# SER_24.net
KiCad netlist of a schematic drawn in Altium Designer
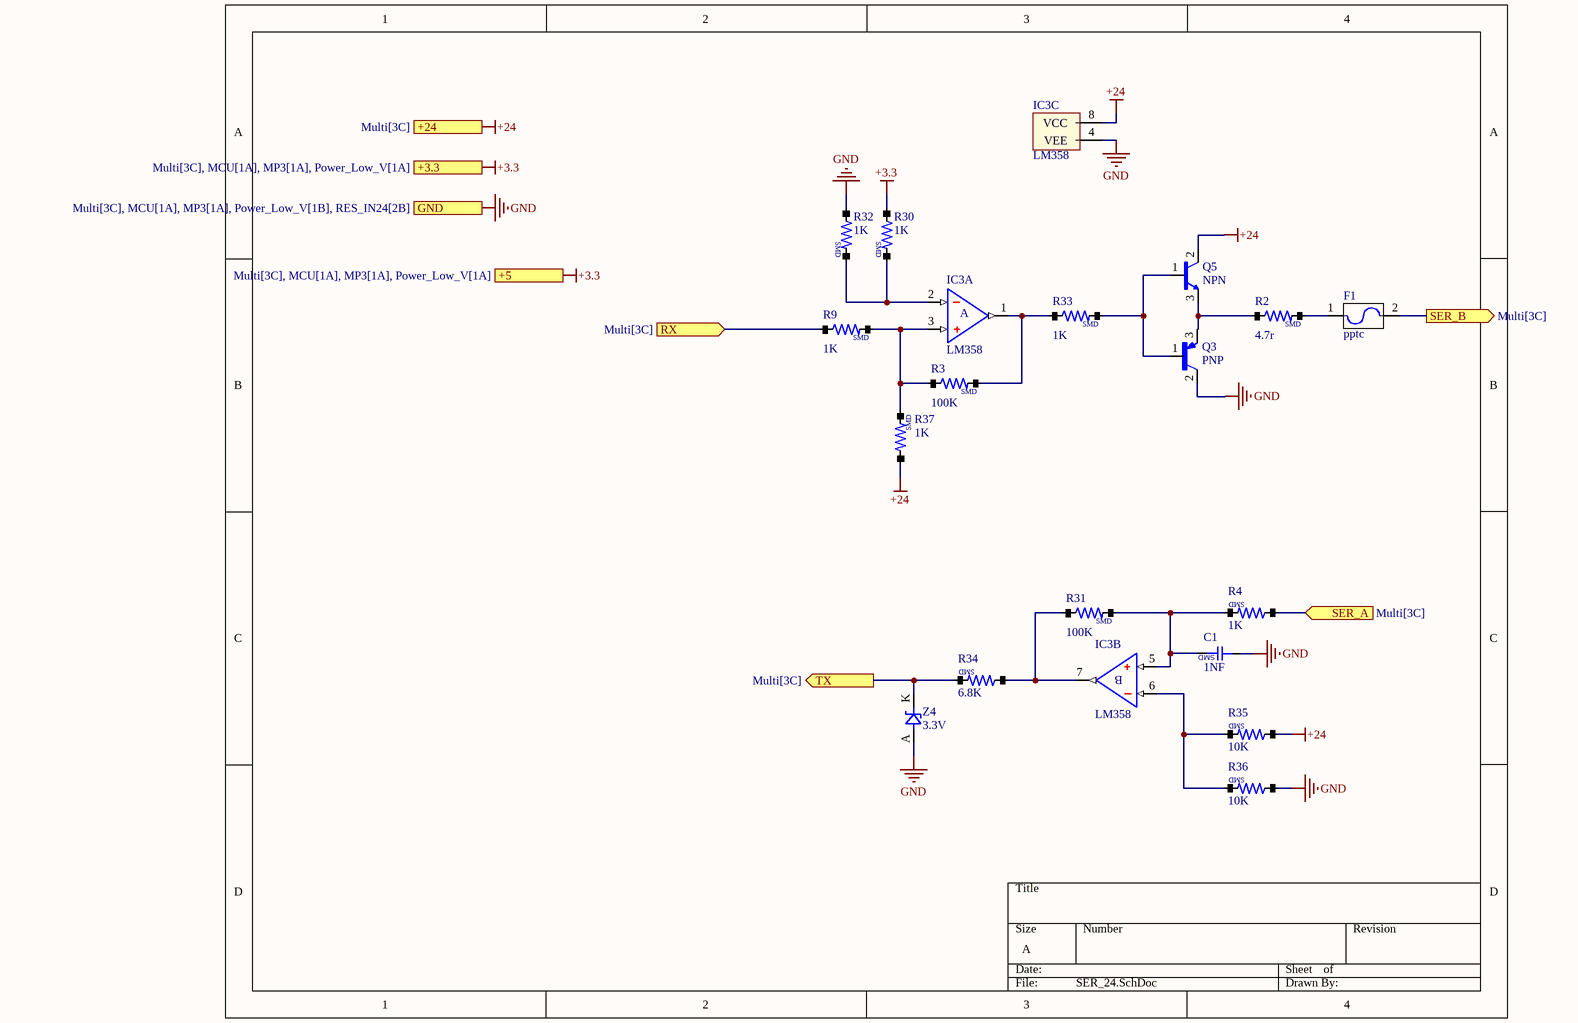
[diagram p0: SER_24.SchDoc]

(export (version "E")
  (design (tool "Eeschema 10.0.6"))
  (components
    (comp (ref "C1") (value "1NF") (footprint "CAP-0603") (libsource (lib "kave-eng-pro") (part "cap_smd")))
    (comp (ref "F1") (value "pptc") (footprint "PPTC") (libsource (lib "kave-eng-pro") (part "fuze")))
    (comp (ref "IC3") (value "LM358") (footprint "SOP-8") (libsource (lib "") (part "LM358_1")))
    (comp (ref "Q3") (value "PNP") (footprint "SOT-89") (libsource (lib "kave-eng-pro") (part "PNP")))
    (comp (ref "Q5") (value "NPN") (footprint "SOT-89") (libsource (lib "kave-eng-pro") (part "NPN")))
    (comp (ref "R2") (value "4.7r") (footprint "RES/0805") (libsource (lib "") (part "RES/SMD_1")))
    (comp (ref "R3") (value "100K") (footprint "RES/0603") (libsource (lib "") (part "RES/SMD_1")))
    (comp (ref "R4") (value "1K") (footprint "RES/0603") (libsource (lib "") (part "RES/SMD_2")))
    (comp (ref "R9") (value "1K") (footprint "RES/0603") (libsource (lib "") (part "RES/SMD_1")))
    (comp (ref "R30") (value "1K") (footprint "RES/0603") (libsource (lib "kave-eng-pro") (part "RES/SMD")))
    (comp (ref "R31") (value "100K") (footprint "RES/0603") (libsource (lib "") (part "RES/SMD_1")))
    (comp (ref "R32") (value "1K") (footprint "RES/0603") (libsource (lib "kave-eng-pro") (part "RES/SMD")))
    (comp (ref "R33") (value "1K") (footprint "RES/0603") (libsource (lib "") (part "RES/SMD_1")))
    (comp (ref "R34") (value "6.8K") (footprint "RES/0805") (libsource (lib "") (part "RES/SMD_2")))
    (comp (ref "R35") (value "10K") (footprint "RES/0603") (libsource (lib "") (part "RES/SMD_2")))
    (comp (ref "R36") (value "10K") (footprint "RES/0603") (libsource (lib "") (part "RES/SMD_2")))
    (comp (ref "R37") (value "1K") (footprint "RES/0603") (libsource (lib "") (part "RES/SMD_3")))
    (comp (ref "Z4")
      (value "3.3V")
      (footprint "DIOD/RS1J")
      (libsource (lib "kave-eng-pro") (part "zener-0.5w"))
    )
  )
  (nets
    (net (code "1") (name "+3.3") (class "Default")
      (node (ref "R30") (pin "1") (pinfunction "1_1") (pintype "passive"))
    )
    (net (code "2") (name "+24") (class "Default")
      (node (ref "IC3") (pin "8") (pinfunction "VCC_8") (pintype "power_in"))
      (node (ref "Q5") (pin "2") (pinfunction "C_2") (pintype "passive"))
      (node (ref "R35") (pin "1") (pinfunction "1_1") (pintype "passive"))
      (node (ref "R37") (pin "1") (pinfunction "1_1") (pintype "passive"))
    )
    (net (code "3") (name "/RX") (class "Default")
      (node (ref "R9") (pin "1") (pinfunction "1_1") (pintype "passive"))
    )
    (net (code "4") (name "/SER_A") (class "Default")
      (node (ref "R4") (pin "1") (pinfunction "1_1") (pintype "passive"))
    )
    (net (code "5") (name "/SER_B") (class "Default") (node (ref "F1") (pin "2") (pintype "passive")))
    (net (code "6") (name "/TX") (class "Default")
      (node (ref "R34") (pin "2") (pinfunction "2_2") (pintype "passive"))
      (node (ref "Z4") (pin "K") (pintype "passive"))
    )
    (net (code "7") (name "GND") (class "Default")
      (node (ref "C1") (pin "1") (pintype "passive"))
      (node (ref "IC3") (pin "4") (pinfunction "VEE_4") (pintype "power_in"))
      (node (ref "Q3") (pin "2") (pinfunction "C_2") (pintype "passive"))
      (node (ref "R32") (pin "1") (pinfunction "1_1") (pintype "passive"))
      (node (ref "R36") (pin "1") (pinfunction "1_1") (pintype "passive"))
      (node (ref "Z4") (pin "A") (pintype "passive"))
    )
    (net (code "8") (name "Net-(C1-Pad2)") (class "Default")
      (node (ref "C1") (pin "2") (pintype "passive"))
      (node (ref "IC3") (pin "5") (pintype "input"))
      (node (ref "R31") (pin "2") (pinfunction "2_2") (pintype "passive"))
      (node (ref "R4") (pin "2") (pinfunction "2_2") (pintype "passive"))
    )
    (net (code "9") (name "Net-(F1-Pad1)") (class "Default")
      (node (ref "F1") (pin "1") (pintype "passive"))
      (node (ref "R2") (pin "2") (pinfunction "2_2") (pintype "passive"))
    )
    (net (code "10") (name "Net-(IC3-Pad1)") (class "Default")
      (node (ref "IC3") (pin "1") (pintype "output"))
      (node (ref "R3") (pin "2") (pinfunction "2_2") (pintype "passive"))
      (node (ref "R33") (pin "1") (pinfunction "1_1") (pintype "passive"))
    )
    (net (code "11") (name "Net-(IC3-Pad2)") (class "Default")
      (node (ref "IC3") (pin "2") (pintype "input"))
      (node (ref "R30") (pin "2") (pinfunction "2_2") (pintype "passive"))
      (node (ref "R32") (pin "2") (pinfunction "2_2") (pintype "passive"))
    )
    (net (code "12") (name "Net-(IC3-Pad3)") (class "Default")
      (node (ref "IC3") (pin "3") (pintype "input"))
      (node (ref "R3") (pin "1") (pinfunction "1_1") (pintype "passive"))
      (node (ref "R37") (pin "2") (pinfunction "2_2") (pintype "passive"))
      (node (ref "R9") (pin "2") (pinfunction "2_2") (pintype "passive"))
    )
    (net (code "13") (name "Net-(IC3-Pad6)") (class "Default")
      (node (ref "IC3") (pin "6") (pintype "input"))
      (node (ref "R35") (pin "2") (pinfunction "2_2") (pintype "passive"))
      (node (ref "R36") (pin "2") (pinfunction "2_2") (pintype "passive"))
    )
    (net (code "14") (name "Net-(IC3-Pad7)") (class "Default")
      (node (ref "IC3") (pin "7") (pintype "output"))
      (node (ref "R31") (pin "1") (pinfunction "1_1") (pintype "passive"))
      (node (ref "R34") (pin "1") (pinfunction "1_1") (pintype "passive"))
    )
    (net (code "15") (name "Net-(Q3-B)") (class "Default")
      (node (ref "Q3") (pin "1") (pinfunction "B_1") (pintype "passive"))
      (node (ref "Q5") (pin "1") (pinfunction "B_1") (pintype "passive"))
      (node (ref "R33") (pin "2") (pinfunction "2_2") (pintype "passive"))
    )
    (net (code "16") (name "Net-(Q3-E)") (class "Default")
      (node (ref "Q3") (pin "3") (pinfunction "E_3") (pintype "passive"))
      (node (ref "Q5") (pin "3") (pinfunction "E_3") (pintype "passive"))
      (node (ref "R2") (pin "1") (pinfunction "1_1") (pintype "passive"))
    )
  )
)
